# NMEA2000-BME280.net
KiCad netlist of a schematic drawn in EAGLE
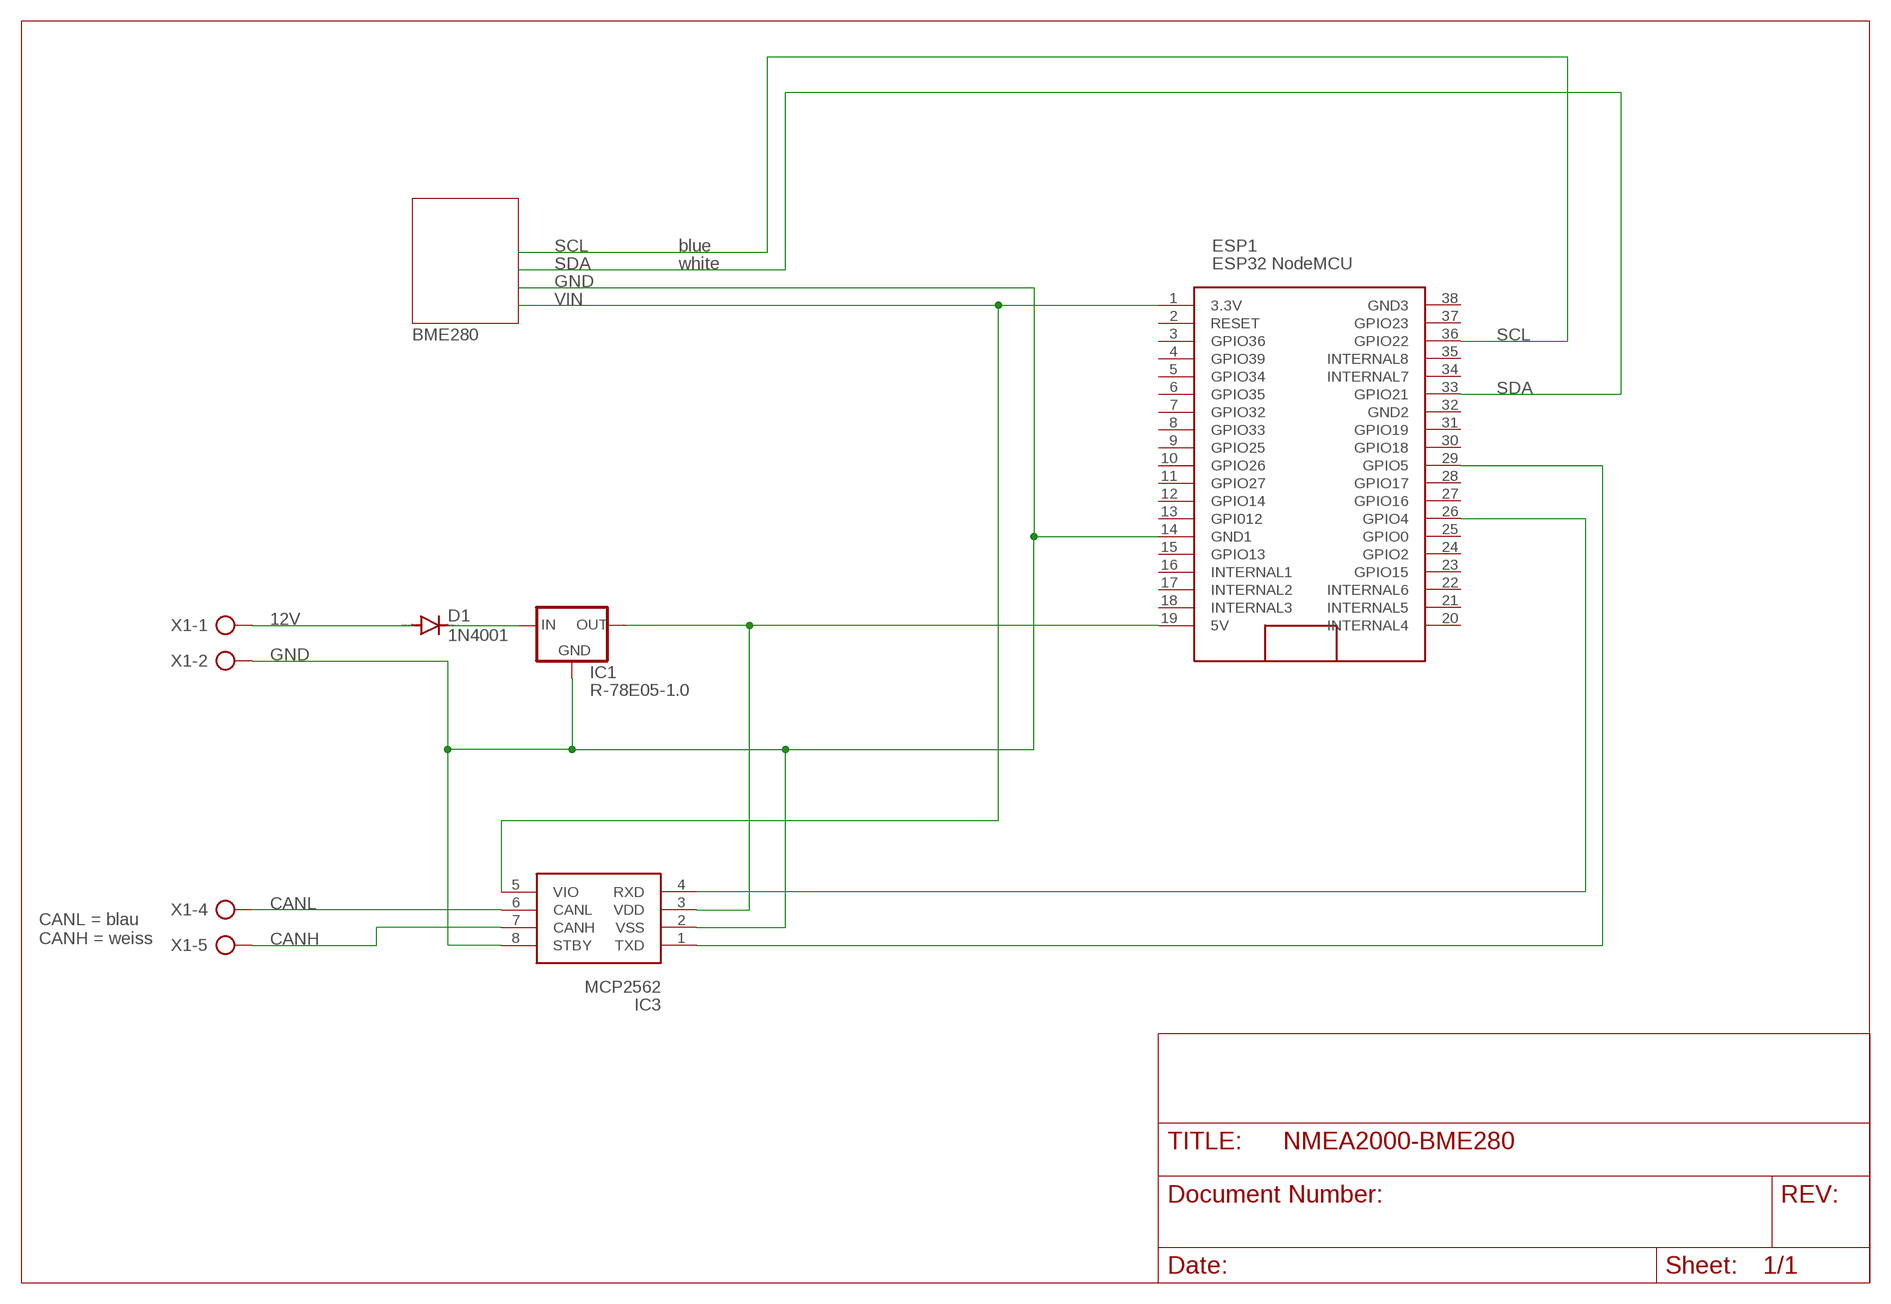
[diagram p0: schematic, sheet 1]

(export (version "E")
  (design (tool "Eeschema 10.0.6"))
  (components
    (comp (ref "D1")
      (value "1N4001")
      (footprint "eagle-import:DO41-10")
      (libsource (lib "eagle-import") (part "1N4004"))
    )
    (comp (ref "ESP1")
      (value "ESP32 NodeMCU")
      (footprint "eagle-import:ESP32_NODEMCU")
      (libsource (lib "eagle-import") (part "ESP32-NODEMCU"))
    )
    (comp (ref "IC1")
      (value "R-78E05-1.0")
      (footprint "eagle-import:78XXS")
      (libsource (lib "eagle-import") (part "78XXS"))
    )
    (comp (ref "IC3")
      (value "MCP2562")
      (footprint "eagle-import:DIL08")
      (libsource (lib "eagle-import") (part "MCP2562"))
    )
    (comp (ref "X1")
      (value "AK500/5")
      (footprint "eagle-import:AK500_5")
      (libsource (lib "eagle-import") (part "AK500/5"))
    )
  )
  (nets
    (net (code "1") (name "/12V") (class "Default")
      (node (ref "D1") (pin "A") (pinfunction "A_A") (pintype "passive"))
      (node (ref "X1") (pin "1") (pinfunction "KL_1") (pintype "passive"))
    )
    (net (code "2") (name "/CANH") (class "Default")
      (node (ref "IC3") (pin "7") (pinfunction "CANH_7") (pintype "bidirectional"))
      (node (ref "X1") (pin "5") (pinfunction "KL_5") (pintype "passive"))
    )
    (net (code "3") (name "/CANL") (class "Default")
      (node (ref "IC3") (pin "6") (pinfunction "CANL_6") (pintype "bidirectional"))
      (node (ref "X1") (pin "4") (pinfunction "KL_4") (pintype "passive"))
    )
    (net (code "4") (name "/GND") (class "Default")
      (node (ref "ESP1") (pin "14") (pinfunction "GND1_14") (pintype "power_in"))
      (node (ref "IC1") (pin "GND") (pinfunction "GND_GND") (pintype "input"))
      (node (ref "IC3") (pin "2") (pinfunction "VSS_2") (pintype "bidirectional"))
      (node (ref "IC3") (pin "8") (pinfunction "STBY_8") (pintype "bidirectional"))
      (node (ref "X1") (pin "2") (pinfunction "KL_2") (pintype "passive"))
    )
    (net (code "5") (name "/GND2") (class "Default")
      (node (ref "ESP1") (pin "32") (pinfunction "GND2_32") (pintype "power_in"))
    )
    (net (code "6") (name "/GND3") (class "Default")
      (node (ref "ESP1") (pin "38") (pinfunction "GND3_38") (pintype "power_in"))
    )
    (net (code "7") (name "/SCL") (class "Default")
      (node (ref "ESP1") (pin "36") (pinfunction "GPIO22_36") (pintype "bidirectional"))
    )
    (net (code "8") (name "/SDA") (class "Default")
      (node (ref "ESP1") (pin "33") (pinfunction "GPIO21_33") (pintype "bidirectional"))
    )
    (net (code "9") (name "/VIN") (class "Default")
      (node (ref "ESP1") (pin "1") (pinfunction "3.3V_1") (pintype "power_in"))
      (node (ref "IC3") (pin "5") (pinfunction "VIO_5") (pintype "bidirectional"))
    )
    (net (code "10") (name "Net-(D1-PadC)") (class "Default")
      (node (ref "D1") (pin "C") (pinfunction "C_C") (pintype "passive"))
      (node (ref "IC1") (pin "IN") (pinfunction "IN_IN") (pintype "input"))
    )
    (net (code "11") (name "Net-(ESP1-5V)") (class "Default")
      (node (ref "ESP1") (pin "19") (pinfunction "5V_19") (pintype "power_in"))
      (node (ref "IC1") (pin "OUT") (pinfunction "OUT_OUT") (pintype "passive"))
      (node (ref "IC3") (pin "3") (pinfunction "VDD_3") (pintype "bidirectional"))
    )
    (net (code "12") (name "Net-(ESP1-GPIO4)") (class "Default")
      (node (ref "ESP1") (pin "26") (pinfunction "GPIO4_26") (pintype "bidirectional"))
      (node (ref "IC3") (pin "4") (pinfunction "RXD_4") (pintype "bidirectional"))
    )
    (net (code "13") (name "Net-(ESP1-GPIO5)") (class "Default")
      (node (ref "ESP1") (pin "29") (pinfunction "GPIO5_29") (pintype "bidirectional"))
      (node (ref "IC3") (pin "1") (pinfunction "TXD_1") (pintype "bidirectional"))
    )
    (net (code "14") (name "unconnected-(ESP1-GPI012-Pad13)") (class "Default")
      (node (ref "ESP1") (pin "13") (pinfunction "GPI012_13") (pintype "bidirectional"))
    )
    (net (code "15") (name "unconnected-(ESP1-GPIO0-Pad25)") (class "Default")
      (node (ref "ESP1") (pin "25") (pinfunction "GPIO0_25") (pintype "output"))
    )
    (net (code "16") (name "unconnected-(ESP1-GPIO2-Pad24)") (class "Default")
      (node (ref "ESP1") (pin "24") (pinfunction "GPIO2_24") (pintype "bidirectional"))
    )
    (net (code "17") (name "unconnected-(ESP1-GPIO13-Pad15)") (class "Default")
      (node (ref "ESP1") (pin "15") (pinfunction "GPIO13_15") (pintype "bidirectional"))
    )
    (net (code "18") (name "unconnected-(ESP1-GPIO14-Pad12)") (class "Default")
      (node (ref "ESP1") (pin "12") (pinfunction "GPIO14_12") (pintype "bidirectional"))
    )
    (net (code "19") (name "unconnected-(ESP1-GPIO15-Pad23)") (class "Default")
      (node (ref "ESP1") (pin "23") (pinfunction "GPIO15_23") (pintype "bidirectional"))
    )
    (net (code "20") (name "unconnected-(ESP1-GPIO16-Pad27)") (class "Default")
      (node (ref "ESP1") (pin "27") (pinfunction "GPIO16_27") (pintype "bidirectional"))
    )
    (net (code "21") (name "unconnected-(ESP1-GPIO17-Pad28)") (class "Default")
      (node (ref "ESP1") (pin "28") (pinfunction "GPIO17_28") (pintype "bidirectional"))
    )
    (net (code "22") (name "unconnected-(ESP1-GPIO18-Pad30)") (class "Default")
      (node (ref "ESP1") (pin "30") (pinfunction "GPIO18_30") (pintype "bidirectional"))
    )
    (net (code "23") (name "unconnected-(ESP1-GPIO19-Pad31)") (class "Default")
      (node (ref "ESP1") (pin "31") (pinfunction "GPIO19_31") (pintype "bidirectional"))
    )
    (net (code "24") (name "unconnected-(ESP1-GPIO23-Pad37)") (class "Default")
      (node (ref "ESP1") (pin "37") (pinfunction "GPIO23_37") (pintype "bidirectional"))
    )
    (net (code "25") (name "unconnected-(ESP1-GPIO25-Pad9)") (class "Default")
      (node (ref "ESP1") (pin "9") (pinfunction "GPIO25_9") (pintype "bidirectional"))
    )
    (net (code "26") (name "unconnected-(ESP1-GPIO26-Pad10)") (class "Default")
      (node (ref "ESP1") (pin "10") (pinfunction "GPIO26_10") (pintype "bidirectional"))
    )
    (net (code "27") (name "unconnected-(ESP1-GPIO27-Pad11)") (class "Default")
      (node (ref "ESP1") (pin "11") (pinfunction "GPIO27_11") (pintype "bidirectional"))
    )
    (net (code "28") (name "unconnected-(ESP1-GPIO32-Pad7)") (class "Default")
      (node (ref "ESP1") (pin "7") (pinfunction "GPIO32_7") (pintype "bidirectional"))
    )
    (net (code "29") (name "unconnected-(ESP1-GPIO33-Pad8)") (class "Default")
      (node (ref "ESP1") (pin "8") (pinfunction "GPIO33_8") (pintype "bidirectional"))
    )
    (net (code "30") (name "unconnected-(ESP1-GPIO34-Pad5)") (class "Default")
      (node (ref "ESP1") (pin "5") (pinfunction "GPIO34_5") (pintype "input"))
    )
    (net (code "31") (name "unconnected-(ESP1-GPIO35-Pad6)") (class "Default")
      (node (ref "ESP1") (pin "6") (pinfunction "GPIO35_6") (pintype "input"))
    )
    (net (code "32") (name "unconnected-(ESP1-GPIO36-Pad3)") (class "Default")
      (node (ref "ESP1") (pin "3") (pinfunction "GPIO36_3") (pintype "input"))
    )
    (net (code "33") (name "unconnected-(ESP1-GPIO39-Pad4)") (class "Default")
      (node (ref "ESP1") (pin "4") (pinfunction "GPIO39_4") (pintype "input"))
    )
    (net (code "34") (name "unconnected-(ESP1-INTERNAL1-Pad16)") (class "Default")
      (node (ref "ESP1") (pin "16") (pinfunction "INTERNAL1_16") (pintype "no_connect"))
    )
    (net (code "35") (name "unconnected-(ESP1-INTERNAL2-Pad17)") (class "Default")
      (node (ref "ESP1") (pin "17") (pinfunction "INTERNAL2_17") (pintype "no_connect"))
    )
    (net (code "36") (name "unconnected-(ESP1-INTERNAL3-Pad18)") (class "Default")
      (node (ref "ESP1") (pin "18") (pinfunction "INTERNAL3_18") (pintype "no_connect"))
    )
    (net (code "37") (name "unconnected-(ESP1-INTERNAL4-Pad20)") (class "Default")
      (node (ref "ESP1") (pin "20") (pinfunction "INTERNAL4_20") (pintype "no_connect"))
    )
    (net (code "38") (name "unconnected-(ESP1-INTERNAL5-Pad21)") (class "Default")
      (node (ref "ESP1") (pin "21") (pinfunction "INTERNAL5_21") (pintype "no_connect"))
    )
    (net (code "39") (name "unconnected-(ESP1-INTERNAL6-Pad22)") (class "Default")
      (node (ref "ESP1") (pin "22") (pinfunction "INTERNAL6_22") (pintype "no_connect"))
    )
    (net (code "40") (name "unconnected-(ESP1-INTERNAL7-Pad34)") (class "Default")
      (node (ref "ESP1") (pin "34") (pinfunction "INTERNAL7_34") (pintype "no_connect"))
    )
    (net (code "41") (name "unconnected-(ESP1-INTERNAL8-Pad35)") (class "Default")
      (node (ref "ESP1") (pin "35") (pinfunction "INTERNAL8_35") (pintype "no_connect"))
    )
    (net (code "42") (name "unconnected-(ESP1-RESET-Pad2)") (class "Default")
      (node (ref "ESP1") (pin "2") (pinfunction "RESET_2") (pintype "input"))
    )
  )
)
